# Sheet2.net
KiCad netlist of a schematic drawn in Altium Designer
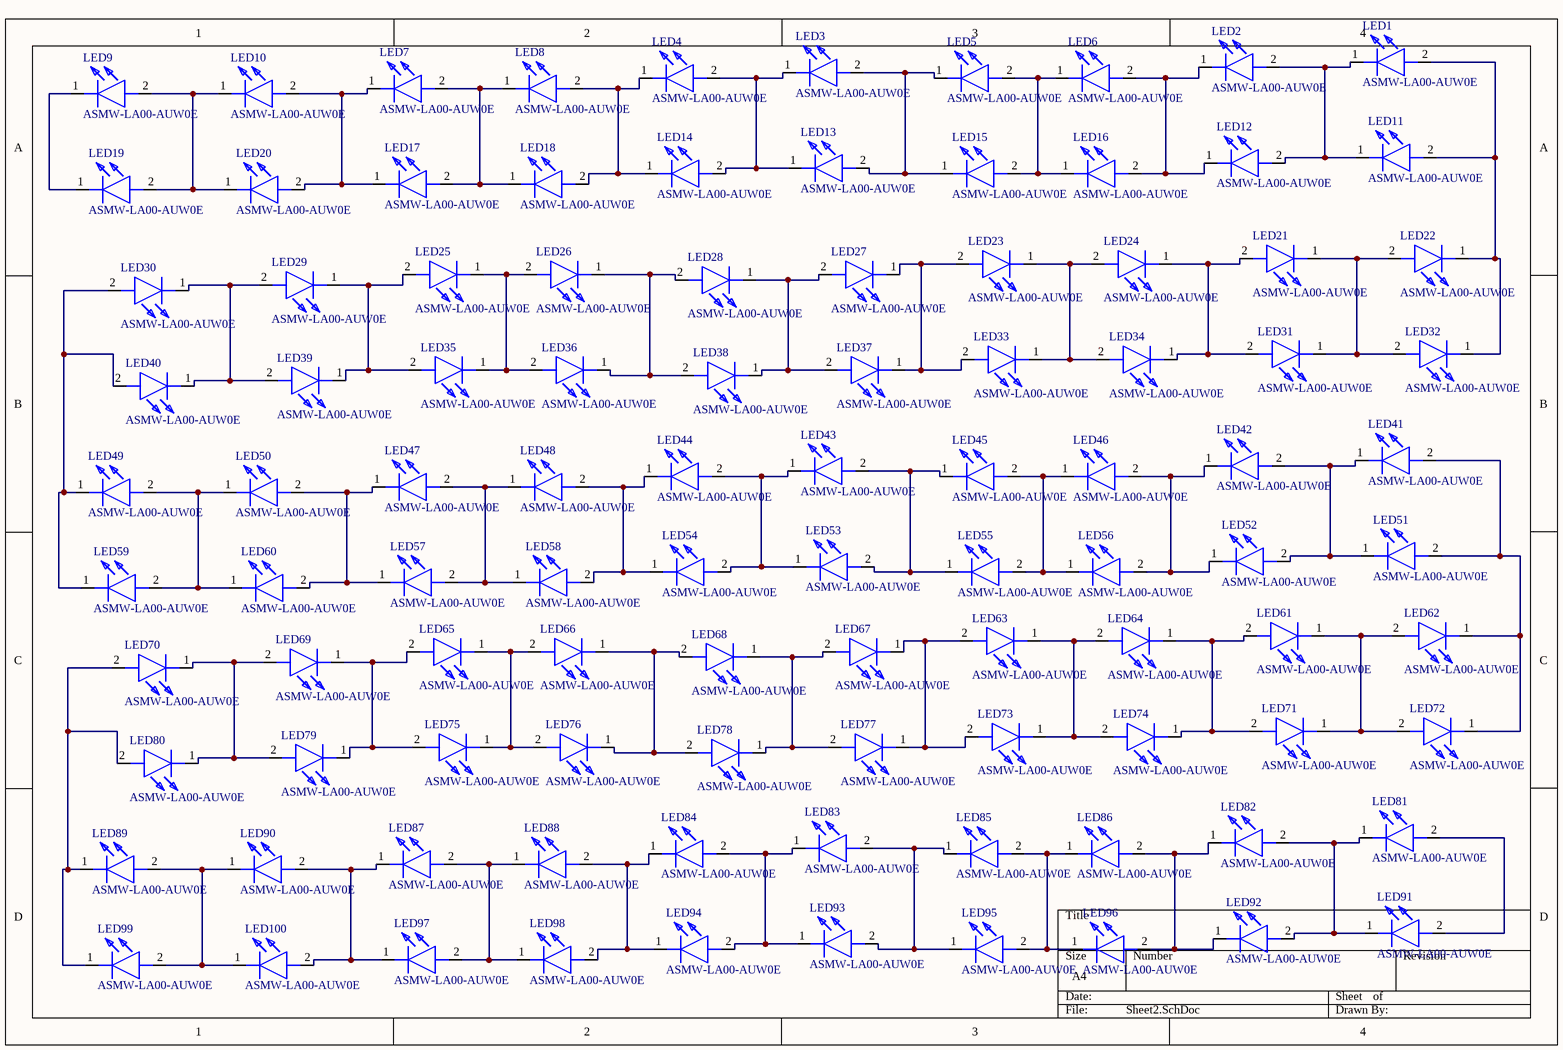
[diagram p0: Sheet2.SchDoc]

(export (version "E")
  (design (tool "Eeschema 10.0.6"))
  (components
    (comp (ref "LED1")
      (value "ASMW-LA00-AUW0E")
      (footprint "SamacSys:ASMWLA00AUW0E")
      (description "LED")
      (fields (field (name "MOUSER PART NUMBER") "630-ASMW-LA00-AUW0E"))
      (libsource (lib "*") (part "ASMW-LA00-AUW0E"))
    )
    (comp (ref "LED2")
      (value "ASMW-LA00-AUW0E")
      (footprint "SamacSys:ASMWLA00AUW0E")
      (description "LED")
      (fields (field (name "MOUSER PART NUMBER") "630-ASMW-LA00-AUW0E"))
      (libsource (lib "*") (part "ASMW-LA00-AUW0E"))
    )
    (comp (ref "LED3")
      (value "ASMW-LA00-AUW0E")
      (footprint "SamacSys:ASMWLA00AUW0E")
      (description "LED")
      (fields (field (name "MOUSER PART NUMBER") "630-ASMW-LA00-AUW0E"))
      (libsource (lib "*") (part "ASMW-LA00-AUW0E"))
    )
    (comp (ref "LED4")
      (value "ASMW-LA00-AUW0E")
      (footprint "SamacSys:ASMWLA00AUW0E")
      (description "LED")
      (fields (field (name "MOUSER PART NUMBER") "630-ASMW-LA00-AUW0E"))
      (libsource (lib "*") (part "ASMW-LA00-AUW0E"))
    )
    (comp (ref "LED5")
      (value "ASMW-LA00-AUW0E")
      (footprint "SamacSys:ASMWLA00AUW0E")
      (description "LED")
      (fields (field (name "MOUSER PART NUMBER") "630-ASMW-LA00-AUW0E"))
      (libsource (lib "*") (part "ASMW-LA00-AUW0E"))
    )
    (comp (ref "LED6")
      (value "ASMW-LA00-AUW0E")
      (footprint "SamacSys:ASMWLA00AUW0E")
      (description "LED")
      (fields (field (name "MOUSER PART NUMBER") "630-ASMW-LA00-AUW0E"))
      (libsource (lib "*") (part "ASMW-LA00-AUW0E"))
    )
    (comp (ref "LED7")
      (value "ASMW-LA00-AUW0E")
      (footprint "SamacSys:ASMWLA00AUW0E")
      (description "LED")
      (fields (field (name "MOUSER PART NUMBER") "630-ASMW-LA00-AUW0E"))
      (libsource (lib "*") (part "ASMW-LA00-AUW0E"))
    )
    (comp (ref "LED8")
      (value "ASMW-LA00-AUW0E")
      (footprint "SamacSys:ASMWLA00AUW0E")
      (description "LED")
      (fields (field (name "MOUSER PART NUMBER") "630-ASMW-LA00-AUW0E"))
      (libsource (lib "*") (part "ASMW-LA00-AUW0E"))
    )
    (comp (ref "LED9")
      (value "ASMW-LA00-AUW0E")
      (footprint "SamacSys:ASMWLA00AUW0E")
      (description "LED")
      (fields (field (name "MOUSER PART NUMBER") "630-ASMW-LA00-AUW0E"))
      (libsource (lib "*") (part "ASMW-LA00-AUW0E"))
    )
    (comp (ref "LED10")
      (value "ASMW-LA00-AUW0E")
      (footprint "SamacSys:ASMWLA00AUW0E")
      (description "LED")
      (fields (field (name "MOUSER PART NUMBER") "630-ASMW-LA00-AUW0E"))
      (libsource (lib "*") (part "ASMW-LA00-AUW0E"))
    )
    (comp (ref "LED11")
      (value "ASMW-LA00-AUW0E")
      (footprint "SamacSys:ASMWLA00AUW0E")
      (description "LED")
      (fields (field (name "MOUSER PART NUMBER") "630-ASMW-LA00-AUW0E"))
      (libsource (lib "*") (part "ASMW-LA00-AUW0E"))
    )
    (comp (ref "LED12")
      (value "ASMW-LA00-AUW0E")
      (footprint "SamacSys:ASMWLA00AUW0E")
      (description "LED")
      (fields (field (name "MOUSER PART NUMBER") "630-ASMW-LA00-AUW0E"))
      (libsource (lib "*") (part "ASMW-LA00-AUW0E"))
    )
    (comp (ref "LED13")
      (value "ASMW-LA00-AUW0E")
      (footprint "SamacSys:ASMWLA00AUW0E")
      (description "LED")
      (fields (field (name "MOUSER PART NUMBER") "630-ASMW-LA00-AUW0E"))
      (libsource (lib "*") (part "ASMW-LA00-AUW0E"))
    )
    (comp (ref "LED14")
      (value "ASMW-LA00-AUW0E")
      (footprint "SamacSys:ASMWLA00AUW0E")
      (description "LED")
      (fields (field (name "MOUSER PART NUMBER") "630-ASMW-LA00-AUW0E"))
      (libsource (lib "*") (part "ASMW-LA00-AUW0E"))
    )
    (comp (ref "LED15")
      (value "ASMW-LA00-AUW0E")
      (footprint "SamacSys:ASMWLA00AUW0E")
      (description "LED")
      (fields (field (name "MOUSER PART NUMBER") "630-ASMW-LA00-AUW0E"))
      (libsource (lib "*") (part "ASMW-LA00-AUW0E"))
    )
    (comp (ref "LED16")
      (value "ASMW-LA00-AUW0E")
      (footprint "SamacSys:ASMWLA00AUW0E")
      (description "LED")
      (fields (field (name "MOUSER PART NUMBER") "630-ASMW-LA00-AUW0E"))
      (libsource (lib "*") (part "ASMW-LA00-AUW0E"))
    )
    (comp (ref "LED17")
      (value "ASMW-LA00-AUW0E")
      (footprint "SamacSys:ASMWLA00AUW0E")
      (description "LED")
      (fields (field (name "MOUSER PART NUMBER") "630-ASMW-LA00-AUW0E"))
      (libsource (lib "*") (part "ASMW-LA00-AUW0E"))
    )
    (comp (ref "LED18")
      (value "ASMW-LA00-AUW0E")
      (footprint "SamacSys:ASMWLA00AUW0E")
      (description "LED")
      (fields (field (name "MOUSER PART NUMBER") "630-ASMW-LA00-AUW0E"))
      (libsource (lib "*") (part "ASMW-LA00-AUW0E"))
    )
    (comp (ref "LED19")
      (value "ASMW-LA00-AUW0E")
      (footprint "SamacSys:ASMWLA00AUW0E")
      (description "LED")
      (fields (field (name "MOUSER PART NUMBER") "630-ASMW-LA00-AUW0E"))
      (libsource (lib "*") (part "ASMW-LA00-AUW0E"))
    )
    (comp (ref "LED20")
      (value "ASMW-LA00-AUW0E")
      (footprint "SamacSys:ASMWLA00AUW0E")
      (description "LED")
      (fields (field (name "MOUSER PART NUMBER") "630-ASMW-LA00-AUW0E"))
      (libsource (lib "*") (part "ASMW-LA00-AUW0E"))
    )
    (comp (ref "LED21")
      (value "ASMW-LA00-AUW0E")
      (footprint "SamacSys:ASMWLA00AUW0E")
      (description "LED")
      (fields (field (name "MOUSER PART NUMBER") "630-ASMW-LA00-AUW0E"))
      (libsource (lib "*") (part "ASMW-LA00-AUW0E"))
    )
    (comp (ref "LED22")
      (value "ASMW-LA00-AUW0E")
      (footprint "SamacSys:ASMWLA00AUW0E")
      (description "LED")
      (fields (field (name "MOUSER PART NUMBER") "630-ASMW-LA00-AUW0E"))
      (libsource (lib "*") (part "ASMW-LA00-AUW0E"))
    )
    (comp (ref "LED23")
      (value "ASMW-LA00-AUW0E")
      (footprint "SamacSys:ASMWLA00AUW0E")
      (description "LED")
      (fields (field (name "MOUSER PART NUMBER") "630-ASMW-LA00-AUW0E"))
      (libsource (lib "*") (part "ASMW-LA00-AUW0E"))
    )
    (comp (ref "LED24")
      (value "ASMW-LA00-AUW0E")
      (footprint "SamacSys:ASMWLA00AUW0E")
      (description "LED")
      (fields (field (name "MOUSER PART NUMBER") "630-ASMW-LA00-AUW0E"))
      (libsource (lib "*") (part "ASMW-LA00-AUW0E"))
    )
    (comp (ref "LED25")
      (value "ASMW-LA00-AUW0E")
      (footprint "SamacSys:ASMWLA00AUW0E")
      (description "LED")
      (fields (field (name "MOUSER PART NUMBER") "630-ASMW-LA00-AUW0E"))
      (libsource (lib "*") (part "ASMW-LA00-AUW0E"))
    )
    (comp (ref "LED26")
      (value "ASMW-LA00-AUW0E")
      (footprint "SamacSys:ASMWLA00AUW0E")
      (description "LED")
      (fields (field (name "MOUSER PART NUMBER") "630-ASMW-LA00-AUW0E"))
      (libsource (lib "*") (part "ASMW-LA00-AUW0E"))
    )
    (comp (ref "LED27")
      (value "ASMW-LA00-AUW0E")
      (footprint "SamacSys:ASMWLA00AUW0E")
      (description "LED")
      (fields (field (name "MOUSER PART NUMBER") "630-ASMW-LA00-AUW0E"))
      (libsource (lib "*") (part "ASMW-LA00-AUW0E"))
    )
    (comp (ref "LED28")
      (value "ASMW-LA00-AUW0E")
      (footprint "SamacSys:ASMWLA00AUW0E")
      (description "LED")
      (fields (field (name "MOUSER PART NUMBER") "630-ASMW-LA00-AUW0E"))
      (libsource (lib "*") (part "ASMW-LA00-AUW0E"))
    )
    (comp (ref "LED29")
      (value "ASMW-LA00-AUW0E")
      (footprint "SamacSys:ASMWLA00AUW0E")
      (description "LED")
      (fields (field (name "MOUSER PART NUMBER") "630-ASMW-LA00-AUW0E"))
      (libsource (lib "*") (part "ASMW-LA00-AUW0E"))
    )
    (comp (ref "LED30")
      (value "ASMW-LA00-AUW0E")
      (footprint "SamacSys:ASMWLA00AUW0E")
      (description "LED")
      (fields (field (name "MOUSER PART NUMBER") "630-ASMW-LA00-AUW0E"))
      (libsource (lib "*") (part "ASMW-LA00-AUW0E"))
    )
    (comp (ref "LED31")
      (value "ASMW-LA00-AUW0E")
      (footprint "SamacSys:ASMWLA00AUW0E")
      (description "LED")
      (fields (field (name "MOUSER PART NUMBER") "630-ASMW-LA00-AUW0E"))
      (libsource (lib "*") (part "ASMW-LA00-AUW0E"))
    )
    (comp (ref "LED32")
      (value "ASMW-LA00-AUW0E")
      (footprint "SamacSys:ASMWLA00AUW0E")
      (description "LED")
      (fields (field (name "MOUSER PART NUMBER") "630-ASMW-LA00-AUW0E"))
      (libsource (lib "*") (part "ASMW-LA00-AUW0E"))
    )
    (comp (ref "LED33")
      (value "ASMW-LA00-AUW0E")
      (footprint "SamacSys:ASMWLA00AUW0E")
      (description "LED")
      (fields (field (name "MOUSER PART NUMBER") "630-ASMW-LA00-AUW0E"))
      (libsource (lib "*") (part "ASMW-LA00-AUW0E"))
    )
    (comp (ref "LED34")
      (value "ASMW-LA00-AUW0E")
      (footprint "SamacSys:ASMWLA00AUW0E")
      (description "LED")
      (fields (field (name "MOUSER PART NUMBER") "630-ASMW-LA00-AUW0E"))
      (libsource (lib "*") (part "ASMW-LA00-AUW0E"))
    )
    (comp (ref "LED35")
      (value "ASMW-LA00-AUW0E")
      (footprint "SamacSys:ASMWLA00AUW0E")
      (description "LED")
      (fields (field (name "MOUSER PART NUMBER") "630-ASMW-LA00-AUW0E"))
      (libsource (lib "*") (part "ASMW-LA00-AUW0E"))
    )
    (comp (ref "LED36")
      (value "ASMW-LA00-AUW0E")
      (footprint "SamacSys:ASMWLA00AUW0E")
      (description "LED")
      (fields (field (name "MOUSER PART NUMBER") "630-ASMW-LA00-AUW0E"))
      (libsource (lib "*") (part "ASMW-LA00-AUW0E"))
    )
    (comp (ref "LED37")
      (value "ASMW-LA00-AUW0E")
      (footprint "SamacSys:ASMWLA00AUW0E")
      (description "LED")
      (fields (field (name "MOUSER PART NUMBER") "630-ASMW-LA00-AUW0E"))
      (libsource (lib "*") (part "ASMW-LA00-AUW0E"))
    )
    (comp (ref "LED38")
      (value "ASMW-LA00-AUW0E")
      (footprint "SamacSys:ASMWLA00AUW0E")
      (description "LED")
      (fields (field (name "MOUSER PART NUMBER") "630-ASMW-LA00-AUW0E"))
      (libsource (lib "*") (part "ASMW-LA00-AUW0E"))
    )
    (comp (ref "LED39")
      (value "ASMW-LA00-AUW0E")
      (footprint "SamacSys:ASMWLA00AUW0E")
      (description "LED")
      (fields (field (name "MOUSER PART NUMBER") "630-ASMW-LA00-AUW0E"))
      (libsource (lib "*") (part "ASMW-LA00-AUW0E"))
    )
    (comp (ref "LED40")
      (value "ASMW-LA00-AUW0E")
      (footprint "SamacSys:ASMWLA00AUW0E")
      (description "LED")
      (fields (field (name "MOUSER PART NUMBER") "630-ASMW-LA00-AUW0E"))
      (libsource (lib "*") (part "ASMW-LA00-AUW0E"))
    )
    (comp (ref "LED41")
      (value "ASMW-LA00-AUW0E")
      (footprint "SamacSys:ASMWLA00AUW0E")
      (description "LED")
      (fields (field (name "MOUSER PART NUMBER") "630-ASMW-LA00-AUW0E"))
      (libsource (lib "*") (part "ASMW-LA00-AUW0E"))
    )
    (comp (ref "LED42")
      (value "ASMW-LA00-AUW0E")
      (footprint "SamacSys:ASMWLA00AUW0E")
      (description "LED")
      (fields (field (name "MOUSER PART NUMBER") "630-ASMW-LA00-AUW0E"))
      (libsource (lib "*") (part "ASMW-LA00-AUW0E"))
    )
    (comp (ref "LED43")
      (value "ASMW-LA00-AUW0E")
      (footprint "SamacSys:ASMWLA00AUW0E")
      (description "LED")
      (fields (field (name "MOUSER PART NUMBER") "630-ASMW-LA00-AUW0E"))
      (libsource (lib "*") (part "ASMW-LA00-AUW0E"))
    )
    (comp (ref "LED44")
      (value "ASMW-LA00-AUW0E")
      (footprint "SamacSys:ASMWLA00AUW0E")
      (description "LED")
      (fields (field (name "MOUSER PART NUMBER") "630-ASMW-LA00-AUW0E"))
      (libsource (lib "*") (part "ASMW-LA00-AUW0E"))
    )
    (comp (ref "LED45")
      (value "ASMW-LA00-AUW0E")
      (footprint "SamacSys:ASMWLA00AUW0E")
      (description "LED")
      (fields (field (name "MOUSER PART NUMBER") "630-ASMW-LA00-AUW0E"))
      (libsource (lib "*") (part "ASMW-LA00-AUW0E"))
    )
    (comp (ref "LED46")
      (value "ASMW-LA00-AUW0E")
      (footprint "SamacSys:ASMWLA00AUW0E")
      (description "LED")
      (fields (field (name "MOUSER PART NUMBER") "630-ASMW-LA00-AUW0E"))
      (libsource (lib "*") (part "ASMW-LA00-AUW0E"))
    )
    (comp (ref "LED47")
      (value "ASMW-LA00-AUW0E")
      (footprint "SamacSys:ASMWLA00AUW0E")
      (description "LED")
      (fields (field (name "MOUSER PART NUMBER") "630-ASMW-LA00-AUW0E"))
      (libsource (lib "*") (part "ASMW-LA00-AUW0E"))
    )
    (comp (ref "LED48")
      (value "ASMW-LA00-AUW0E")
      (footprint "SamacSys:ASMWLA00AUW0E")
      (description "LED")
      (fields (field (name "MOUSER PART NUMBER") "630-ASMW-LA00-AUW0E"))
      (libsource (lib "*") (part "ASMW-LA00-AUW0E"))
    )
    (comp (ref "LED49")
      (value "ASMW-LA00-AUW0E")
      (footprint "SamacSys:ASMWLA00AUW0E")
      (description "LED")
      (fields (field (name "MOUSER PART NUMBER") "630-ASMW-LA00-AUW0E"))
      (libsource (lib "*") (part "ASMW-LA00-AUW0E"))
    )
    (comp (ref "LED50")
      (value "ASMW-LA00-AUW0E")
      (footprint "SamacSys:ASMWLA00AUW0E")
      (description "LED")
      (fields (field (name "MOUSER PART NUMBER") "630-ASMW-LA00-AUW0E"))
      (libsource (lib "*") (part "ASMW-LA00-AUW0E"))
    )
    (comp (ref "LED51")
      (value "ASMW-LA00-AUW0E")
      (footprint "SamacSys:ASMWLA00AUW0E")
      (description "LED")
      (fields (field (name "MOUSER PART NUMBER") "630-ASMW-LA00-AUW0E"))
      (libsource (lib "*") (part "ASMW-LA00-AUW0E"))
    )
    (comp (ref "LED52")
      (value "ASMW-LA00-AUW0E")
      (footprint "SamacSys:ASMWLA00AUW0E")
      (description "LED")
      (fields (field (name "MOUSER PART NUMBER") "630-ASMW-LA00-AUW0E"))
      (libsource (lib "*") (part "ASMW-LA00-AUW0E"))
    )
    (comp (ref "LED53")
      (value "ASMW-LA00-AUW0E")
      (footprint "SamacSys:ASMWLA00AUW0E")
      (description "LED")
      (fields (field (name "MOUSER PART NUMBER") "630-ASMW-LA00-AUW0E"))
      (libsource (lib "*") (part "ASMW-LA00-AUW0E"))
    )
    (comp (ref "LED54")
      (value "ASMW-LA00-AUW0E")
      (footprint "SamacSys:ASMWLA00AUW0E")
      (description "LED")
      (fields (field (name "MOUSER PART NUMBER") "630-ASMW-LA00-AUW0E"))
      (libsource (lib "*") (part "ASMW-LA00-AUW0E"))
    )
    (comp (ref "LED55")
      (value "ASMW-LA00-AUW0E")
      (footprint "SamacSys:ASMWLA00AUW0E")
      (description "LED")
      (fields (field (name "MOUSER PART NUMBER") "630-ASMW-LA00-AUW0E"))
      (libsource (lib "*") (part "ASMW-LA00-AUW0E"))
    )
    (comp (ref "LED56")
      (value "ASMW-LA00-AUW0E")
      (footprint "SamacSys:ASMWLA00AUW0E")
      (description "LED")
      (fields (field (name "MOUSER PART NUMBER") "630-ASMW-LA00-AUW0E"))
      (libsource (lib "*") (part "ASMW-LA00-AUW0E"))
    )
    (comp (ref "LED57")
      (value "ASMW-LA00-AUW0E")
      (footprint "SamacSys:ASMWLA00AUW0E")
      (description "LED")
      (fields (field (name "MOUSER PART NUMBER") "630-ASMW-LA00-AUW0E"))
      (libsource (lib "*") (part "ASMW-LA00-AUW0E"))
    )
    (comp (ref "LED58")
      (value "ASMW-LA00-AUW0E")
      (footprint "SamacSys:ASMWLA00AUW0E")
      (description "LED")
      (fields (field (name "MOUSER PART NUMBER") "630-ASMW-LA00-AUW0E"))
      (libsource (lib "*") (part "ASMW-LA00-AUW0E"))
    )
    (comp (ref "LED59")
      (value "ASMW-LA00-AUW0E")
      (footprint "SamacSys:ASMWLA00AUW0E")
      (description "LED")
      (fields (field (name "MOUSER PART NUMBER") "630-ASMW-LA00-AUW0E"))
      (libsource (lib "*") (part "ASMW-LA00-AUW0E"))
    )
    (comp (ref "LED60")
      (value "ASMW-LA00-AUW0E")
      (footprint "SamacSys:ASMWLA00AUW0E")
      (description "LED")
      (fields (field (name "MOUSER PART NUMBER") "630-ASMW-LA00-AUW0E"))
      (libsource (lib "*") (part "ASMW-LA00-AUW0E"))
    )
    (comp (ref "LED61")
      (value "ASMW-LA00-AUW0E")
      (footprint "SamacSys:ASMWLA00AUW0E")
      (description "LED")
      (fields (field (name "MOUSER PART NUMBER") "630-ASMW-LA00-AUW0E"))
      (libsource (lib "*") (part "ASMW-LA00-AUW0E"))
    )
    (comp (ref "LED62")
      (value "ASMW-LA00-AUW0E")
      (footprint "SamacSys:ASMWLA00AUW0E")
      (description "LED")
      (fields (field (name "MOUSER PART NUMBER") "630-ASMW-LA00-AUW0E"))
      (libsource (lib "*") (part "ASMW-LA00-AUW0E"))
    )
    (comp (ref "LED63")
      (value "ASMW-LA00-AUW0E")
      (footprint "SamacSys:ASMWLA00AUW0E")
      (description "LED")
      (fields (field (name "MOUSER PART NUMBER") "630-ASMW-LA00-AUW0E"))
      (libsource (lib "*") (part "ASMW-LA00-AUW0E"))
    )
    (comp (ref "LED64")
      (value "ASMW-LA00-AUW0E")
      (footprint "SamacSys:ASMWLA00AUW0E")
      (description "LED")
      (fields (field (name "MOUSER PART NUMBER") "630-ASMW-LA00-AUW0E"))
      (libsource (lib "*") (part "ASMW-LA00-AUW0E"))
    )
    (comp (ref "LED65")
      (value "ASMW-LA00-AUW0E")
      (footprint "SamacSys:ASMWLA00AUW0E")
      (description "LED")
      (fields (field (name "MOUSER PART NUMBER") "630-ASMW-LA00-AUW0E"))
      (libsource (lib "*") (part "ASMW-LA00-AUW0E"))
    )
    (comp (ref "LED66")
      (value "ASMW-LA00-AUW0E")
      (footprint "SamacSys:ASMWLA00AUW0E")
      (description "LED")
      (fields (field (name "MOUSER PART NUMBER") "630-ASMW-LA00-AUW0E"))
      (libsource (lib "*") (part "ASMW-LA00-AUW0E"))
    )
    (comp (ref "LED67")
      (value "ASMW-LA00-AUW0E")
      (footprint "SamacSys:ASMWLA00AUW0E")
      (description "LED")
      (fields (field (name "MOUSER PART NUMBER") "630-ASMW-LA00-AUW0E"))
      (libsource (lib "*") (part "ASMW-LA00-AUW0E"))
    )
    (comp (ref "LED68")
      (value "ASMW-LA00-AUW0E")
      (footprint "SamacSys:ASMWLA00AUW0E")
      (description "LED")
      (fields (field (name "MOUSER PART NUMBER") "630-ASMW-LA00-AUW0E"))
      (libsource (lib "*") (part "ASMW-LA00-AUW0E"))
    )
    (comp (ref "LED69")
      (value "ASMW-LA00-AUW0E")
      (footprint "SamacSys:ASMWLA00AUW0E")
      (description "LED")
      (fields (field (name "MOUSER PART NUMBER") "630-ASMW-LA00-AUW0E"))
      (libsource (lib "*") (part "ASMW-LA00-AUW0E"))
    )
    (comp (ref "LED70")
      (value "ASMW-LA00-AUW0E")
      (footprint "SamacSys:ASMWLA00AUW0E")
      (description "LED")
      (fields (field (name "MOUSER PART NUMBER") "630-ASMW-LA00-AUW0E"))
      (libsource (lib "*") (part "ASMW-LA00-AUW0E"))
    )
    (comp (ref "LED71")
      (value "ASMW-LA00-AUW0E")
      (footprint "SamacSys:ASMWLA00AUW0E")
      (description "LED")
      (fields (field (name "MOUSER PART NUMBER") "630-ASMW-LA00-AUW0E"))
      (libsource (lib "*") (part "ASMW-LA00-AUW0E"))
    )
    (comp (ref "LED72")
      (value "ASMW-LA00-AUW0E")
      (footprint "SamacSys:ASMWLA00AUW0E")
      (description "LED")
      (fields (field (name "MOUSER PART NUMBER") "630-ASMW-LA00-AUW0E"))
      (libsource (lib "*") (part "ASMW-LA00-AUW0E"))
    )
    (comp (ref "LED73")
      (value "ASMW-LA00-AUW0E")
      (footprint "SamacSys:ASMWLA00AUW0E")
      (description "LED")
      (fields (field (name "MOUSER PART NUMBER") "630-ASMW-LA00-AUW0E"))
      (libsource (lib "*") (part "ASMW-LA00-AUW0E"))
    )
    (comp (ref "LED74")
      (value "ASMW-LA00-AUW0E")
      (footprint "SamacSys:ASMWLA00AUW0E")
      (description "LED")
      (fields (field (name "MOUSER PART NUMBER") "630-ASMW-LA00-AUW0E"))
      (libsource (lib "*") (part "ASMW-LA00-AUW0E"))
    )
    (comp (ref "LED75")
      (value "ASMW-LA00-AUW0E")
      (footprint "SamacSys:ASMWLA00AUW0E")
      (description "LED")
      (fields (field (name "MOUSER PART NUMBER") "630-ASMW-LA00-AUW0E"))
      (libsource (lib "*") (part "ASMW-LA00-AUW0E"))
    )
    (comp (ref "LED76")
      (value "ASMW-LA00-AUW0E")
      (footprint "SamacSys:ASMWLA00AUW0E")
      (description "LED")
      (fields (field (name "MOUSER PART NUMBER") "630-ASMW-LA00-AUW0E"))
      (libsource (lib "*") (part "ASMW-LA00-AUW0E"))
    )
    (comp (ref "LED77")
      (value "ASMW-LA00-AUW0E")
      (footprint "SamacSys:ASMWLA00AUW0E")
      (description "LED")
      (fields (field (name "MOUSER PART NUMBER") "630-ASMW-LA00-AUW0E"))
      (libsource (lib "*") (part "ASMW-LA00-AUW0E"))
    )
    (comp (ref "LED78")
      (value "ASMW-LA00-AUW0E")
      (footprint "SamacSys:ASMWLA00AUW0E")
      (description "LED")
      (fields (field (name "MOUSER PART NUMBER") "630-ASMW-LA00-AUW0E"))
      (libsource (lib "*") (part "ASMW-LA00-AUW0E"))
    )
    (comp (ref "LED79")
      (value "ASMW-LA00-AUW0E")
      (footprint "SamacSys:ASMWLA00AUW0E")
      (description "LED")
      (fields (field (name "MOUSER PART NUMBER") "630-ASMW-LA00-AUW0E"))
      (libsource (lib "*") (part "ASMW-LA00-AUW0E"))
    )
    (comp (ref "LED80")
      (value "ASMW-LA00-AUW0E")
      (footprint "SamacSys:ASMWLA00AUW0E")
      (description "LED")
      (fields (field (name "MOUSER PART NUMBER") "630-ASMW-LA00-AUW0E"))
      (libsource (lib "*") (part "ASMW-LA00-AUW0E"))
    )
    (comp (ref "LED81")
      (value "ASMW-LA00-AUW0E")
      (footprint "SamacSys:ASMWLA00AUW0E")
      (description "LED")
      (fields (field (name "MOUSER PART NUMBER") "630-ASMW-LA00-AUW0E"))
      (libsource (lib "*") (part "ASMW-LA00-AUW0E"))
    )
    (comp (ref "LED82")
      (value "ASMW-LA00-AUW0E")
      (footprint "SamacSys:ASMWLA00AUW0E")
      (description "LED")
      (fields (field (name "MOUSER PART NUMBER") "630-ASMW-LA00-AUW0E"))
      (libsource (lib "*") (part "ASMW-LA00-AUW0E"))
    )
    (comp (ref "LED83")
      (value "ASMW-LA00-AUW0E")
      (footprint "SamacSys:ASMWLA00AUW0E")
      (description "LED")
      (fields (field (name "MOUSER PART NUMBER") "630-ASMW-LA00-AUW0E"))
      (libsource (lib "*") (part "ASMW-LA00-AUW0E"))
    )
    (comp (ref "LED84")
      (value "ASMW-LA00-AUW0E")
      (footprint "SamacSys:ASMWLA00AUW0E")
      (description "LED")
      (fields (field (name "MOUSER PART NUMBER") "630-ASMW-LA00-AUW0E"))
      (libsource (lib "*") (part "ASMW-LA00-AUW0E"))
    )
    (comp (ref "LED85")
      (value "ASMW-LA00-AUW0E")
      (footprint "SamacSys:ASMWLA00AUW0E")
      (description "LED")
      (fields (field (name "MOUSER PART NUMBER") "630-ASMW-LA00-AUW0E"))
      (libsource (lib "*") (part "ASMW-LA00-AUW0E"))
    )
    (comp (ref "LED86")
      (value "ASMW-LA00-AUW0E")
      (footprint "SamacSys:ASMWLA00AUW0E")
      (description "LED")
      (fields (field (name "MOUSER PART NUMBER") "630-ASMW-LA00-AUW0E"))
      (libsource (lib "*") (part "ASMW-LA00-AUW0E"))
    )
    (comp (ref "LED87")
      (value "ASMW-LA00-AUW0E")
      (footprint "SamacSys:ASMWLA00AUW0E")
      (description "LED")
      (fields (field (name "MOUSER PART NUMBER") "630-ASMW-LA00-AUW0E"))
      (libsource (lib "*") (part "ASMW-LA00-AUW0E"))
    )
    (comp (ref "LED88")
      (value "ASMW-LA00-AUW0E")
      (footprint "SamacSys:ASMWLA00AUW0E")
      (description "LED")
      (fields (field (name "MOUSER PART NUMBER") "630-ASMW-LA00-AUW0E"))
      (libsource (lib "*") (part "ASMW-LA00-AUW0E"))
    )
    (comp (ref "LED89")
      (value "ASMW-LA00-AUW0E")
      (footprint "SamacSys:ASMWLA00AUW0E")
      (description "LED")
      (fields (field (name "MOUSER PART NUMBER") "630-ASMW-LA00-AUW0E"))
      (libsource (lib "*") (part "ASMW-LA00-AUW0E"))
    )
    (comp (ref "LED90")
      (value "ASMW-LA00-AUW0E")
      (footprint "SamacSys:ASMWLA00AUW0E")
      (description "LED")
      (fields (field (name "MOUSER PART NUMBER") "630-ASMW-LA00-AUW0E"))
      (libsource (lib "*") (part "ASMW-LA00-AUW0E"))
    )
    (comp (ref "LED91")
      (value "ASMW-LA00-AUW0E")
      (footprint "SamacSys:ASMWLA00AUW0E")
      (description "LED")
      (fields (field (name "MOUSER PART NUMBER") "630-ASMW-LA00-AUW0E"))
      (libsource (lib "*") (part "ASMW-LA00-AUW0E"))
    )
    (comp (ref "LED92")
      (value "ASMW-LA00-AUW0E")
      (footprint "SamacSys:ASMWLA00AUW0E")
      (description "LED")
      (fields (field (name "MOUSER PART NUMBER") "630-ASMW-LA00-AUW0E"))
      (libsource (lib "*") (part "ASMW-LA00-AUW0E"))
    )
    (comp (ref "LED93")
      (value "ASMW-LA00-AUW0E")
      (footprint "SamacSys:ASMWLA00AUW0E")
      (description "LED")
      (fields (field (name "MOUSER PART NUMBER") "630-ASMW-LA00-AUW0E"))
      (libsource (lib "*") (part "ASMW-LA00-AUW0E"))
    )
    (comp (ref "LED94")
      (value "ASMW-LA00-AUW0E")
      (footprint "SamacSys:ASMWLA00AUW0E")
      (description "LED")
      (fields (field (name "MOUSER PART NUMBER") "630-ASMW-LA00-AUW0E"))
      (libsource (lib "*") (part "ASMW-LA00-AUW0E"))
    )
    (comp (ref "LED95")
      (value "ASMW-LA00-AUW0E")
      (footprint "SamacSys:ASMWLA00AUW0E")
      (description "LED")
      (fields (field (name "MOUSER PART NUMBER") "630-ASMW-LA00-AUW0E"))
      (libsource (lib "*") (part "ASMW-LA00-AUW0E"))
    )
    (comp (ref "LED96")
      (value "ASMW-LA00-AUW0E")
      (footprint "SamacSys:ASMWLA00AUW0E")
      (description "LED")
      (fields (field (name "MOUSER PART NUMBER") "630-ASMW-LA00-AUW0E"))
      (libsource (lib "*") (part "ASMW-LA00-AUW0E"))
    )
    (comp (ref "LED97")
      (value "ASMW-LA00-AUW0E")
      (footprint "SamacSys:ASMWLA00AUW0E")
      (description "LED")
      (fields (field (name "MOUSER PART NUMBER") "630-ASMW-LA00-AUW0E"))
      (libsource (lib "*") (part "ASMW-LA00-AUW0E"))
    )
    (comp (ref "LED98")
      (value "ASMW-LA00-AUW0E")
      (footprint "SamacSys:ASMWLA00AUW0E")
      (description "LED")
      (fields (field (name "MOUSER PART NUMBER") "630-ASMW-LA00-AUW0E"))
      (libsource (lib "*") (part "ASMW-LA00-AUW0E"))
    )
    (comp (ref "LED99")
      (value "ASMW-LA00-AUW0E")
      (footprint "SamacSys:ASMWLA00AUW0E")
      (description "LED")
      (fields (field (name "MOUSER PART NUMBER") "630-ASMW-LA00-AUW0E"))
      (libsource (lib "*") (part "ASMW-LA00-AUW0E"))
    )
    (comp (ref "LED100")
      (value "ASMW-LA00-AUW0E")
      (footprint "SamacSys:ASMWLA00AUW0E")
      (description "LED")
      (fields (field (name "MOUSER PART NUMBER") "630-ASMW-LA00-AUW0E"))
      (libsource (lib "*") (part "ASMW-LA00-AUW0E"))
    )
  )
  (nets
    (net (code "1") (name "Net-(LED1-A)") (class "Default")
      (node (ref "LED1") (pin "2") (pinfunction "A_2") (pintype "passive"))
      (node (ref "LED11") (pin "2") (pinfunction "A_2") (pintype "passive"))
      (node (ref "LED22") (pin "1") (pinfunction "K_1") (pintype "passive"))
      (node (ref "LED32") (pin "1") (pinfunction "K_1") (pintype "passive"))
    )
    (net (code "2") (name "Net-(LED1-K)") (class "Default")
      (node (ref "LED1") (pin "1") (pinfunction "K_1") (pintype "passive"))
      (node (ref "LED11") (pin "1") (pinfunction "K_1") (pintype "passive"))
      (node (ref "LED12") (pin "2") (pinfunction "A_2") (pintype "passive"))
      (node (ref "LED2") (pin "2") (pinfunction "A_2") (pintype "passive"))
    )
    (net (code "3") (name "Net-(LED10-A)") (class "Default")
      (node (ref "LED10") (pin "2") (pinfunction "A_2") (pintype "passive"))
      (node (ref "LED17") (pin "1") (pinfunction "K_1") (pintype "passive"))
      (node (ref "LED20") (pin "2") (pinfunction "A_2") (pintype "passive"))
      (node (ref "LED7") (pin "1") (pinfunction "K_1") (pintype "passive"))
    )
    (net (code "4") (name "Net-(LED10-K)") (class "Default")
      (node (ref "LED10") (pin "1") (pinfunction "K_1") (pintype "passive"))
      (node (ref "LED19") (pin "2") (pinfunction "A_2") (pintype "passive"))
      (node (ref "LED20") (pin "1") (pinfunction "K_1") (pintype "passive"))
      (node (ref "LED9") (pin "2") (pinfunction "A_2") (pintype "passive"))
    )
    (net (code "5") (name "Net-(LED12-K)") (class "Default")
      (node (ref "LED12") (pin "1") (pinfunction "K_1") (pintype "passive"))
      (node (ref "LED16") (pin "2") (pinfunction "A_2") (pintype "passive"))
      (node (ref "LED2") (pin "1") (pinfunction "K_1") (pintype "passive"))
      (node (ref "LED6") (pin "2") (pinfunction "A_2") (pintype "passive"))
    )
    (net (code "6") (name "Net-(LED13-A)") (class "Default")
      (node (ref "LED13") (pin "2") (pinfunction "A_2") (pintype "passive"))
      (node (ref "LED15") (pin "1") (pinfunction "K_1") (pintype "passive"))
      (node (ref "LED3") (pin "2") (pinfunction "A_2") (pintype "passive"))
      (node (ref "LED5") (pin "1") (pinfunction "K_1") (pintype "passive"))
    )
    (net (code "7") (name "Net-(LED13-K)") (class "Default")
      (node (ref "LED13") (pin "1") (pinfunction "K_1") (pintype "passive"))
      (node (ref "LED14") (pin "2") (pinfunction "A_2") (pintype "passive"))
      (node (ref "LED3") (pin "1") (pinfunction "K_1") (pintype "passive"))
      (node (ref "LED4") (pin "2") (pinfunction "A_2") (pintype "passive"))
    )
    (net (code "8") (name "Net-(LED14-K)") (class "Default")
      (node (ref "LED14") (pin "1") (pinfunction "K_1") (pintype "passive"))
      (node (ref "LED18") (pin "2") (pinfunction "A_2") (pintype "passive"))
      (node (ref "LED4") (pin "1") (pinfunction "K_1") (pintype "passive"))
      (node (ref "LED8") (pin "2") (pinfunction "A_2") (pintype "passive"))
    )
    (net (code "9") (name "Net-(LED15-A)") (class "Default")
      (node (ref "LED15") (pin "2") (pinfunction "A_2") (pintype "passive"))
      (node (ref "LED16") (pin "1") (pinfunction "K_1") (pintype "passive"))
      (node (ref "LED5") (pin "2") (pinfunction "A_2") (pintype "passive"))
      (node (ref "LED6") (pin "1") (pinfunction "K_1") (pintype "passive"))
    )
    (net (code "10") (name "Net-(LED17-A)") (class "Default")
      (node (ref "LED17") (pin "2") (pinfunction "A_2") (pintype "passive"))
      (node (ref "LED18") (pin "1") (pinfunction "K_1") (pintype "passive"))
      (node (ref "LED7") (pin "2") (pinfunction "A_2") (pintype "passive"))
      (node (ref "LED8") (pin "1") (pinfunction "K_1") (pintype "passive"))
    )
    (net (code "11") (name "Net-(LED19-K)") (class "Default")
      (node (ref "LED19") (pin "1") (pinfunction "K_1") (pintype "passive"))
      (node (ref "LED9") (pin "1") (pinfunction "K_1") (pintype "passive"))
    )
    (net (code "12") (name "Net-(LED21-A)") (class "Default")
      (node (ref "LED21") (pin "2") (pinfunction "A_2") (pintype "passive"))
      (node (ref "LED24") (pin "1") (pinfunction "K_1") (pintype "passive"))
      (node (ref "LED31") (pin "2") (pinfunction "A_2") (pintype "passive"))
      (node (ref "LED34") (pin "1") (pinfunction "K_1") (pintype "passive"))
    )
    (net (code "13") (name "Net-(LED21-K)") (class "Default")
      (node (ref "LED21") (pin "1") (pinfunction "K_1") (pintype "passive"))
      (node (ref "LED22") (pin "2") (pinfunction "A_2") (pintype "passive"))
      (node (ref "LED31") (pin "1") (pinfunction "K_1") (pintype "passive"))
      (node (ref "LED32") (pin "2") (pinfunction "A_2") (pintype "passive"))
    )
    (net (code "14") (name "Net-(LED23-A)") (class "Default")
      (node (ref "LED23") (pin "2") (pinfunction "A_2") (pintype "passive"))
      (node (ref "LED27") (pin "1") (pinfunction "K_1") (pintype "passive"))
      (node (ref "LED33") (pin "2") (pinfunction "A_2") (pintype "passive"))
      (node (ref "LED37") (pin "1") (pinfunction "K_1") (pintype "passive"))
    )
    (net (code "15") (name "Net-(LED23-K)") (class "Default")
      (node (ref "LED23") (pin "1") (pinfunction "K_1") (pintype "passive"))
      (node (ref "LED24") (pin "2") (pinfunction "A_2") (pintype "passive"))
      (node (ref "LED33") (pin "1") (pinfunction "K_1") (pintype "passive"))
      (node (ref "LED34") (pin "2") (pinfunction "A_2") (pintype "passive"))
    )
    (net (code "16") (name "Net-(LED25-A)") (class "Default")
      (node (ref "LED25") (pin "2") (pinfunction "A_2") (pintype "passive"))
      (node (ref "LED29") (pin "1") (pinfunction "K_1") (pintype "passive"))
      (node (ref "LED35") (pin "2") (pinfunction "A_2") (pintype "passive"))
      (node (ref "LED39") (pin "1") (pinfunction "K_1") (pintype "passive"))
    )
    (net (code "17") (name "Net-(LED25-K)") (class "Default")
      (node (ref "LED25") (pin "1") (pinfunction "K_1") (pintype "passive"))
      (node (ref "LED26") (pin "2") (pinfunction "A_2") (pintype "passive"))
      (node (ref "LED35") (pin "1") (pinfunction "K_1") (pintype "passive"))
      (node (ref "LED36") (pin "2") (pinfunction "A_2") (pintype "passive"))
    )
    (net (code "18") (name "Net-(LED26-K)") (class "Default")
      (node (ref "LED26") (pin "1") (pinfunction "K_1") (pintype "passive"))
      (node (ref "LED28") (pin "2") (pinfunction "A_2") (pintype "passive"))
      (node (ref "LED36") (pin "1") (pinfunction "K_1") (pintype "passive"))
      (node (ref "LED38") (pin "2") (pinfunction "A_2") (pintype "passive"))
    )
    (net (code "19") (name "Net-(LED27-A)") (class "Default")
      (node (ref "LED27") (pin "2") (pinfunction "A_2") (pintype "passive"))
      (node (ref "LED28") (pin "1") (pinfunction "K_1") (pintype "passive"))
      (node (ref "LED37") (pin "2") (pinfunction "A_2") (pintype "passive"))
      (node (ref "LED38") (pin "1") (pinfunction "K_1") (pintype "passive"))
    )
    (net (code "20") (name "Net-(LED29-A)") (class "Default")
      (node (ref "LED29") (pin "2") (pinfunction "A_2") (pintype "passive"))
      (node (ref "LED30") (pin "1") (pinfunction "K_1") (pintype "passive"))
      (node (ref "LED39") (pin "2") (pinfunction "A_2") (pintype "passive"))
      (node (ref "LED40") (pin "1") (pinfunction "K_1") (pintype "passive"))
    )
    (net (code "21") (name "Net-(LED30-A)") (class "Default")
      (node (ref "LED30") (pin "2") (pinfunction "A_2") (pintype "passive"))
      (node (ref "LED40") (pin "2") (pinfunction "A_2") (pintype "passive"))
      (node (ref "LED49") (pin "1") (pinfunction "K_1") (pintype "passive"))
      (node (ref "LED59") (pin "1") (pinfunction "K_1") (pintype "passive"))
    )
    (net (code "22") (name "Net-(LED41-A)") (class "Default")
      (node (ref "LED41") (pin "2") (pinfunction "A_2") (pintype "passive"))
      (node (ref "LED51") (pin "2") (pinfunction "A_2") (pintype "passive"))
      (node (ref "LED62") (pin "1") (pinfunction "K_1") (pintype "passive"))
      (node (ref "LED72") (pin "1") (pinfunction "K_1") (pintype "passive"))
    )
    (net (code "23") (name "Net-(LED41-K)") (class "Default")
      (node (ref "LED41") (pin "1") (pinfunction "K_1") (pintype "passive"))
      (node (ref "LED42") (pin "2") (pinfunction "A_2") (pintype "passive"))
      (node (ref "LED51") (pin "1") (pinfunction "K_1") (pintype "passive"))
      (node (ref "LED52") (pin "2") (pinfunction "A_2") (pintype "passive"))
    )
    (net (code "24") (name "Net-(LED42-K)") (class "Default")
      (node (ref "LED42") (pin "1") (pinfunction "K_1") (pintype "passive"))
      (node (ref "LED46") (pin "2") (pinfunction "A_2") (pintype "passive"))
      (node (ref "LED52") (pin "1") (pinfunction "K_1") (pintype "passive"))
      (node (ref "LED56") (pin "2") (pinfunction "A_2") (pintype "passive"))
    )
    (net (code "25") (name "Net-(LED43-A)") (class "Default")
      (node (ref "LED43") (pin "2") (pinfunction "A_2") (pintype "passive"))
      (node (ref "LED45") (pin "1") (pinfunction "K_1") (pintype "passive"))
      (node (ref "LED53") (pin "2") (pinfunction "A_2") (pintype "passive"))
      (node (ref "LED55") (pin "1") (pinfunction "K_1") (pintype "passive"))
    )
    (net (code "26") (name "Net-(LED43-K)") (class "Default")
      (node (ref "LED43") (pin "1") (pinfunction "K_1") (pintype "passive"))
      (node (ref "LED44") (pin "2") (pinfunction "A_2") (pintype "passive"))
      (node (ref "LED53") (pin "1") (pinfunction "K_1") (pintype "passive"))
      (node (ref "LED54") (pin "2") (pinfunction "A_2") (pintype "passive"))
    )
    (net (code "27") (name "Net-(LED44-K)") (class "Default")
      (node (ref "LED44") (pin "1") (pinfunction "K_1") (pintype "passive"))
      (node (ref "LED48") (pin "2") (pinfunction "A_2") (pintype "passive"))
      (node (ref "LED54") (pin "1") (pinfunction "K_1") (pintype "passive"))
      (node (ref "LED58") (pin "2") (pinfunction "A_2") (pintype "passive"))
    )
    (net (code "28") (name "Net-(LED45-A)") (class "Default")
      (node (ref "LED45") (pin "2") (pinfunction "A_2") (pintype "passive"))
      (node (ref "LED46") (pin "1") (pinfunction "K_1") (pintype "passive"))
      (node (ref "LED55") (pin "2") (pinfunction "A_2") (pintype "passive"))
      (node (ref "LED56") (pin "1") (pinfunction "K_1") (pintype "passive"))
    )
    (net (code "29") (name "Net-(LED47-A)") (class "Default")
      (node (ref "LED47") (pin "2") (pinfunction "A_2") (pintype "passive"))
      (node (ref "LED48") (pin "1") (pinfunction "K_1") (pintype "passive"))
      (node (ref "LED57") (pin "2") (pinfunction "A_2") (pintype "passive"))
      (node (ref "LED58") (pin "1") (pinfunction "K_1") (pintype "passive"))
    )
    (net (code "30") (name "Net-(LED47-K)") (class "Default")
      (node (ref "LED47") (pin "1") (pinfunction "K_1") (pintype "passive"))
      (node (ref "LED50") (pin "2") (pinfunction "A_2") (pintype "passive"))
      (node (ref "LED57") (pin "1") (pinfunction "K_1") (pintype "passive"))
      (node (ref "LED60") (pin "2") (pinfunction "A_2") (pintype "passive"))
    )
    (net (code "31") (name "Net-(LED49-A)") (class "Default")
      (node (ref "LED49") (pin "2") (pinfunction "A_2") (pintype "passive"))
      (node (ref "LED50") (pin "1") (pinfunction "K_1") (pintype "passive"))
      (node (ref "LED59") (pin "2") (pinfunction "A_2") (pintype "passive"))
      (node (ref "LED60") (pin "1") (pinfunction "K_1") (pintype "passive"))
    )
    (net (code "32") (name "Net-(LED61-A)") (class "Default")
      (node (ref "LED61") (pin "2") (pinfunction "A_2") (pintype "passive"))
      (node (ref "LED64") (pin "1") (pinfunction "K_1") (pintype "passive"))
      (node (ref "LED71") (pin "2") (pinfunction "A_2") (pintype "passive"))
      (node (ref "LED74") (pin "1") (pinfunction "K_1") (pintype "passive"))
    )
    (net (code "33") (name "Net-(LED61-K)") (class "Default")
      (node (ref "LED61") (pin "1") (pinfunction "K_1") (pintype "passive"))
      (node (ref "LED62") (pin "2") (pinfunction "A_2") (pintype "passive"))
      (node (ref "LED71") (pin "1") (pinfunction "K_1") (pintype "passive"))
      (node (ref "LED72") (pin "2") (pinfunction "A_2") (pintype "passive"))
    )
    (net (code "34") (name "Net-(LED63-A)") (class "Default")
      (node (ref "LED63") (pin "2") (pinfunction "A_2") (pintype "passive"))
      (node (ref "LED67") (pin "1") (pinfunction "K_1") (pintype "passive"))
      (node (ref "LED73") (pin "2") (pinfunction "A_2") (pintype "passive"))
      (node (ref "LED77") (pin "1") (pinfunction "K_1") (pintype "passive"))
    )
    (net (code "35") (name "Net-(LED63-K)") (class "Default")
      (node (ref "LED63") (pin "1") (pinfunction "K_1") (pintype "passive"))
      (node (ref "LED64") (pin "2") (pinfunction "A_2") (pintype "passive"))
      (node (ref "LED73") (pin "1") (pinfunction "K_1") (pintype "passive"))
      (node (ref "LED74") (pin "2") (pinfunction "A_2") (pintype "passive"))
    )
    (net (code "36") (name "Net-(LED65-A)") (class "Default")
      (node (ref "LED65") (pin "2") (pinfunction "A_2") (pintype "passive"))
      (node (ref "LED69") (pin "1") (pinfunction "K_1") (pintype "passive"))
      (node (ref "LED75") (pin "2") (pinfunction "A_2") (pintype "passive"))
      (node (ref "LED79") (pin "1") (pinfunction "K_1") (pintype "passive"))
    )
    (net (code "37") (name "Net-(LED65-K)") (class "Default")
      (node (ref "LED65") (pin "1") (pinfunction "K_1") (pintype "passive"))
      (node (ref "LED66") (pin "2") (pinfunction "A_2") (pintype "passive"))
      (node (ref "LED75") (pin "1") (pinfunction "K_1") (pintype "passive"))
      (node (ref "LED76") (pin "2") (pinfunction "A_2") (pintype "passive"))
    )
    (net (code "38") (name "Net-(LED66-K)") (class "Default")
      (node (ref "LED66") (pin "1") (pinfunction "K_1") (pintype "passive"))
      (node (ref "LED68") (pin "2") (pinfunction "A_2") (pintype "passive"))
      (node (ref "LED76") (pin "1") (pinfunction "K_1") (pintype "passive"))
      (node (ref "LED78") (pin "2") (pinfunction "A_2") (pintype "passive"))
    )
    (net (code "39") (name "Net-(LED67-A)") (class "Default")
      (node (ref "LED67") (pin "2") (pinfunction "A_2") (pintype "passive"))
      (node (ref "LED68") (pin "1") (pinfunction "K_1") (pintype "passive"))
      (node (ref "LED77") (pin "2") (pinfunction "A_2") (pintype "passive"))
      (node (ref "LED78") (pin "1") (pinfunction "K_1") (pintype "passive"))
    )
    (net (code "40") (name "Net-(LED69-A)") (class "Default")
      (node (ref "LED69") (pin "2") (pinfunction "A_2") (pintype "passive"))
      (node (ref "LED70") (pin "1") (pinfunction "K_1") (pintype "passive"))
      (node (ref "LED79") (pin "2") (pinfunction "A_2") (pintype "passive"))
      (node (ref "LED80") (pin "1") (pinfunction "K_1") (pintype "passive"))
    )
    (net (code "41") (name "Net-(LED70-A)") (class "Default")
      (node (ref "LED70") (pin "2") (pinfunction "A_2") (pintype "passive"))
      (node (ref "LED80") (pin "2") (pinfunction "A_2") (pintype "passive"))
      (node (ref "LED89") (pin "1") (pinfunction "K_1") (pintype "passive"))
      (node (ref "LED99") (pin "1") (pinfunction "K_1") (pintype "passive"))
    )
    (net (code "42") (name "Net-(LED81-A)") (class "Default")
      (node (ref "LED81") (pin "2") (pinfunction "A_2") (pintype "passive"))
      (node (ref "LED91") (pin "2") (pinfunction "A_2") (pintype "passive"))
    )
    (net (code "43") (name "Net-(LED81-K)") (class "Default")
      (node (ref "LED81") (pin "1") (pinfunction "K_1") (pintype "passive"))
      (node (ref "LED82") (pin "2") (pinfunction "A_2") (pintype "passive"))
      (node (ref "LED91") (pin "1") (pinfunction "K_1") (pintype "passive"))
      (node (ref "LED92") (pin "2") (pinfunction "A_2") (pintype "passive"))
    )
    (net (code "44") (name "Net-(LED82-K)") (class "Default")
      (node (ref "LED82") (pin "1") (pinfunction "K_1") (pintype "passive"))
      (node (ref "LED86") (pin "2") (pinfunction "A_2") (pintype "passive"))
      (node (ref "LED92") (pin "1") (pinfunction "K_1") (pintype "passive"))
      (node (ref "LED96") (pin "2") (pinfunction "A_2") (pintype "passive"))
    )
    (net (code "45") (name "Net-(LED83-A)") (class "Default")
      (node (ref "LED83") (pin "2") (pinfunction "A_2") (pintype "passive"))
      (node (ref "LED85") (pin "1") (pinfunction "K_1") (pintype "passive"))
      (node (ref "LED93") (pin "2") (pinfunction "A_2") (pintype "passive"))
      (node (ref "LED95") (pin "1") (pinfunction "K_1") (pintype "passive"))
    )
    (net (code "46") (name "Net-(LED83-K)") (class "Default")
      (node (ref "LED83") (pin "1") (pinfunction "K_1") (pintype "passive"))
      (node (ref "LED84") (pin "2") (pinfunction "A_2") (pintype "passive"))
      (node (ref "LED93") (pin "1") (pinfunction "K_1") (pintype "passive"))
      (node (ref "LED94") (pin "2") (pinfunction "A_2") (pintype "passive"))
    )
    (net (code "47") (name "Net-(LED84-K)") (class "Default")
      (node (ref "LED84") (pin "1") (pinfunction "K_1") (pintype "passive"))
      (node (ref "LED88") (pin "2") (pinfunction "A_2") (pintype "passive"))
      (node (ref "LED94") (pin "1") (pinfunction "K_1") (pintype "passive"))
      (node (ref "LED98") (pin "2") (pinfunction "A_2") (pintype "passive"))
    )
    (net (code "48") (name "Net-(LED85-A)") (class "Default")
      (node (ref "LED85") (pin "2") (pinfunction "A_2") (pintype "passive"))
      (node (ref "LED86") (pin "1") (pinfunction "K_1") (pintype "passive"))
      (node (ref "LED95") (pin "2") (pinfunction "A_2") (pintype "passive"))
      (node (ref "LED96") (pin "1") (pinfunction "K_1") (pintype "passive"))
    )
    (net (code "49") (name "Net-(LED87-A)") (class "Default")
      (node (ref "LED87") (pin "2") (pinfunction "A_2") (pintype "passive"))
      (node (ref "LED88") (pin "1") (pinfunction "K_1") (pintype "passive"))
      (node (ref "LED97") (pin "2") (pinfunction "A_2") (pintype "passive"))
      (node (ref "LED98") (pin "1") (pinfunction "K_1") (pintype "passive"))
    )
    (net (code "50") (name "Net-(LED100-A)") (class "Default")
      (node (ref "LED100") (pin "2") (pinfunction "A_2") (pintype "passive"))
      (node (ref "LED87") (pin "1") (pinfunction "K_1") (pintype "passive"))
      (node (ref "LED90") (pin "2") (pinfunction "A_2") (pintype "passive"))
      (node (ref "LED97") (pin "1") (pinfunction "K_1") (pintype "passive"))
    )
    (net (code "51") (name "Net-(LED100-K)") (class "Default")
      (node (ref "LED100") (pin "1") (pinfunction "K_1") (pintype "passive"))
      (node (ref "LED89") (pin "2") (pinfunction "A_2") (pintype "passive"))
      (node (ref "LED90") (pin "1") (pinfunction "K_1") (pintype "passive"))
      (node (ref "LED99") (pin "2") (pinfunction "A_2") (pintype "passive"))
    )
  )
)
